# rgb-led-board.net
KiCad netlist of a schematic drawn in EAGLE
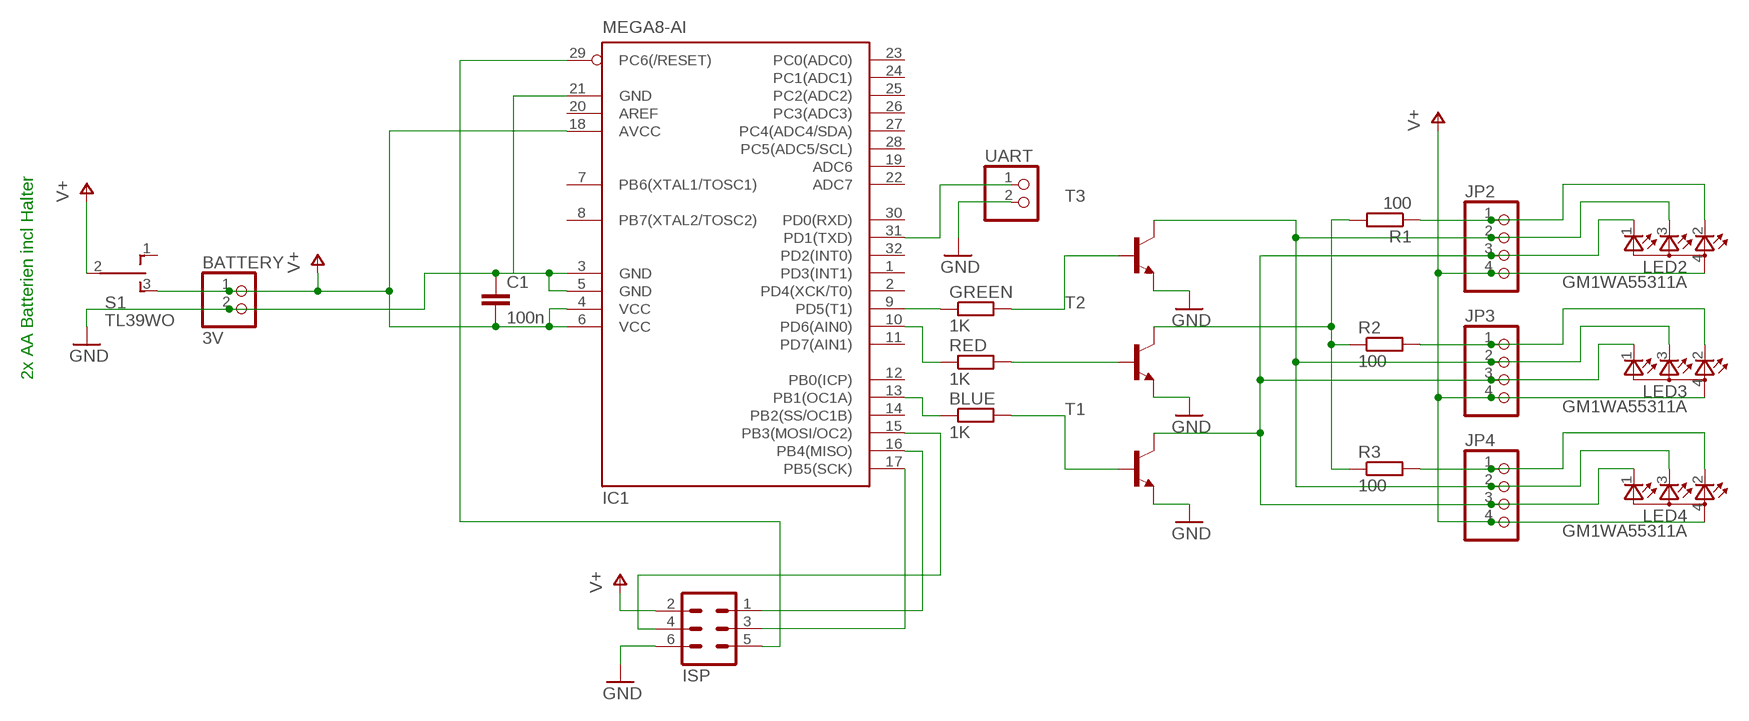
[diagram p0: schematic, sheet 1]

(export (version "E")
  (design (tool "Eeschema 10.0.6"))
  (components
    (comp (ref "BATTERY")
      (value "3V")
      (footprint "eagle-import:1X02")
      (libsource (lib "eagle-import") (part "PINHD-1X2"))
    )
    (comp (ref "BLUE")
      (value "1K")
      (footprint "eagle-import:R1206")
      (libsource (lib "eagle-import") (part "R-EU_R1206"))
    )
    (comp (ref "C1")
      (value "100n")
      (footprint "eagle-import:C1206")
      (libsource (lib "eagle-import") (part "C-EUC1206"))
    )
    (comp (ref "GREEN")
      (value "1K")
      (footprint "eagle-import:R1206")
      (libsource (lib "eagle-import") (part "R-EU_R1206"))
    )
    (comp (ref "IC1")
      (value "MEGA8-AI")
      (footprint "eagle-import:TQFP32-08")
      (fields (field (name "MPN") "ATMEGA8-16AU"))
      (libsource (lib "eagle-import") (part "MEGA8-AI"))
    )
    (comp (ref "ISP")
      (value "ML6")
      (footprint "eagle-import:ML6")
      (libsource (lib "eagle-import") (part "ML6"))
    )
    (comp (ref "JP2")
      (value "PINHD-1X4")
      (footprint "eagle-import:1X04")
      (libsource (lib "eagle-import") (part "PINHD-1X4"))
    )
    (comp (ref "JP3")
      (value "PINHD-1X4")
      (footprint "eagle-import:1X04")
      (libsource (lib "eagle-import") (part "PINHD-1X4"))
    )
    (comp (ref "JP4")
      (value "PINHD-1X4")
      (footprint "eagle-import:1X04")
      (libsource (lib "eagle-import") (part "PINHD-1X4"))
    )
    (comp (ref "LED2")
      (value "GM1WA55311A")
      (footprint "eagle-import:GM1WA55311A")
      (libsource (lib "eagle-import") (part "GM1WA55311A"))
    )
    (comp (ref "LED3")
      (value "GM1WA55311A")
      (footprint "eagle-import:GM1WA55311A")
      (libsource (lib "eagle-import") (part "GM1WA55311A"))
    )
    (comp (ref "LED4")
      (value "GM1WA55311A")
      (footprint "eagle-import:GM1WA55311A")
      (libsource (lib "eagle-import") (part "GM1WA55311A"))
    )
    (comp (ref "R1")
      (value "100")
      (footprint "eagle-import:R1206")
      (libsource (lib "eagle-import") (part "R-EU_R1206"))
    )
    (comp (ref "R2")
      (value "100")
      (footprint "eagle-import:R1206")
      (libsource (lib "eagle-import") (part "R-EU_R1206"))
    )
    (comp (ref "R3")
      (value "100")
      (footprint "eagle-import:R1206")
      (libsource (lib "eagle-import") (part "R-EU_R1206"))
    )
    (comp (ref "RED")
      (value "1K")
      (footprint "eagle-import:R1206")
      (libsource (lib "eagle-import") (part "R-EU_R1206"))
    )
    (comp (ref "S1")
      (value "TL39WO")
      (footprint "eagle-import:TL3XWO")
      (libsource (lib "eagle-import") (part "TL39WO"))
    )
    (comp (ref "T1")
      (value "BC817-16-NPN-SOT23-BEC")
      (footprint "eagle-import:SOT23-BEC")
      (libsource (lib "eagle-import") (part "-NPN-SOT23-BECBC817-16"))
    )
    (comp (ref "T2")
      (value "BC817-16-NPN-SOT23-BEC")
      (footprint "eagle-import:SOT23-BEC")
      (libsource (lib "eagle-import") (part "-NPN-SOT23-BECBC817-16"))
    )
    (comp (ref "T3")
      (value "BC817-16-NPN-SOT23-BEC")
      (footprint "eagle-import:SOT23-BEC")
      (libsource (lib "eagle-import") (part "-NPN-SOT23-BECBC817-16"))
    )
    (comp (ref "UART")
      (value "PINHD-1X2")
      (footprint "eagle-import:1X02")
      (libsource (lib "eagle-import") (part "PINHD-1X2"))
    )
  )
  (nets
    (net (code "1") (name "GND") (class "Default")
      (node (ref "BATTERY") (pin "2") (pinfunction "2_2") (pintype "passive"))
      (node (ref "C1") (pin "1") (pinfunction "1_1") (pintype "passive"))
      (node (ref "IC1") (pin "21") (pinfunction "GND_21") (pintype "power_in"))
      (node (ref "IC1") (pin "3") (pinfunction "GND_3") (pintype "power_in"))
      (node (ref "IC1") (pin "5") (pinfunction "GND_5") (pintype "power_in"))
      (node (ref "ISP") (pin "6") (pinfunction "6_6") (pintype "passive"))
      (node (ref "T1") (pin "E") (pinfunction "E_E") (pintype "passive"))
      (node (ref "T2") (pin "E") (pinfunction "E_E") (pintype "passive"))
      (node (ref "T3") (pin "E") (pinfunction "E_E") (pintype "passive"))
      (node (ref "UART") (pin "2") (pinfunction "2_2") (pintype "passive"))
    )
    (net (code "2") (name "Net-(BLUE-Pad2)") (class "Default")
      (node (ref "BLUE") (pin "2") (pinfunction "2_2") (pintype "passive"))
      (node (ref "T1") (pin "B") (pinfunction "B_B") (pintype "passive"))
    )
    (net (code "3") (name "Net-(GREEN-Pad2)") (class "Default")
      (node (ref "GREEN") (pin "2") (pinfunction "2_2") (pintype "passive"))
      (node (ref "T3") (pin "B") (pinfunction "B_B") (pintype "passive"))
    )
    (net (code "4") (name "Net-(IC1-PB1(OC1A))") (class "Default")
      (node (ref "BLUE") (pin "1") (pinfunction "1_1") (pintype "passive"))
      (node (ref "IC1") (pin "13") (pinfunction "PB1(OC1A)_13") (pintype "bidirectional"))
    )
    (net (code "5") (name "Net-(IC1-PB3(MOSI{slash}OC2))") (class "Default")
      (node (ref "IC1") (pin "15") (pinfunction "PB3(MOSI/OC2)_15") (pintype "bidirectional"))
      (node (ref "ISP") (pin "4") (pinfunction "4_4") (pintype "passive"))
    )
    (net (code "6") (name "Net-(IC1-PB4(MISO))") (class "Default")
      (node (ref "IC1") (pin "16") (pinfunction "PB4(MISO)_16") (pintype "bidirectional"))
      (node (ref "ISP") (pin "1") (pinfunction "1_1") (pintype "passive"))
    )
    (net (code "7") (name "Net-(IC1-PB5(SCK))") (class "Default")
      (node (ref "IC1") (pin "17") (pinfunction "PB5(SCK)_17") (pintype "bidirectional"))
      (node (ref "ISP") (pin "3") (pinfunction "3_3") (pintype "passive"))
    )
    (net (code "8") (name "Net-(IC1-PC6({slash}RESET))") (class "Default")
      (node (ref "IC1") (pin "29") (pinfunction "PC6(/RESET)_29") (pintype "bidirectional"))
      (node (ref "ISP") (pin "5") (pinfunction "5_5") (pintype "passive"))
    )
    (net (code "9") (name "Net-(IC1-PD1(TXD))") (class "Default")
      (node (ref "IC1") (pin "31") (pinfunction "PD1(TXD)_31") (pintype "bidirectional"))
      (node (ref "UART") (pin "1") (pinfunction "1_1") (pintype "passive"))
    )
    (net (code "10") (name "Net-(IC1-PD5(T1))") (class "Default")
      (node (ref "GREEN") (pin "1") (pinfunction "1_1") (pintype "passive"))
      (node (ref "IC1") (pin "9") (pinfunction "PD5(T1)_9") (pintype "bidirectional"))
    )
    (net (code "11") (name "Net-(IC1-PD6(AIN0))") (class "Default")
      (node (ref "IC1") (pin "10") (pinfunction "PD6(AIN0)_10") (pintype "bidirectional"))
      (node (ref "RED") (pin "1") (pinfunction "1_1") (pintype "passive"))
    )
    (net (code "12") (name "Net-(LED2-CBLUE)") (class "Default")
      (node (ref "JP2") (pin "2") (pinfunction "2_2") (pintype "passive"))
      (node (ref "JP3") (pin "2") (pinfunction "2_2") (pintype "passive"))
      (node (ref "JP4") (pin "2") (pinfunction "2_2") (pintype "passive"))
      (node (ref "LED2") (pin "3") (pinfunction "CBLUE_3") (pintype "passive"))
      (node (ref "LED3") (pin "3") (pinfunction "CBLUE_3") (pintype "passive"))
      (node (ref "LED4") (pin "3") (pinfunction "CBLUE_3") (pintype "passive"))
      (node (ref "T3") (pin "C") (pinfunction "C_C") (pintype "passive"))
    )
    (net (code "13") (name "Net-(LED2-CGREEN)") (class "Default")
      (node (ref "JP2") (pin "3") (pinfunction "3_3") (pintype "passive"))
      (node (ref "JP3") (pin "3") (pinfunction "3_3") (pintype "passive"))
      (node (ref "JP4") (pin "3") (pinfunction "3_3") (pintype "passive"))
      (node (ref "LED2") (pin "1") (pinfunction "CGREEN_1") (pintype "passive"))
      (node (ref "LED3") (pin "1") (pinfunction "CGREEN_1") (pintype "passive"))
      (node (ref "LED4") (pin "1") (pinfunction "CGREEN_1") (pintype "passive"))
      (node (ref "T1") (pin "C") (pinfunction "C_C") (pintype "passive"))
    )
    (net (code "14") (name "Net-(LED2-CRED)") (class "Default")
      (node (ref "JP2") (pin "1") (pinfunction "1_1") (pintype "passive"))
      (node (ref "LED2") (pin "2") (pinfunction "CRED_2") (pintype "passive"))
      (node (ref "R1") (pin "1") (pinfunction "1_1") (pintype "passive"))
    )
    (net (code "15") (name "Net-(LED3-CRED)") (class "Default")
      (node (ref "JP3") (pin "1") (pinfunction "1_1") (pintype "passive"))
      (node (ref "LED3") (pin "2") (pinfunction "CRED_2") (pintype "passive"))
      (node (ref "R2") (pin "2") (pinfunction "2_2") (pintype "passive"))
    )
    (net (code "16") (name "Net-(LED4-CRED)") (class "Default")
      (node (ref "JP4") (pin "1") (pinfunction "1_1") (pintype "passive"))
      (node (ref "LED4") (pin "2") (pinfunction "CRED_2") (pintype "passive"))
      (node (ref "R3") (pin "2") (pinfunction "2_2") (pintype "passive"))
    )
    (net (code "17") (name "Net-(R1-Pad2)") (class "Default")
      (node (ref "R1") (pin "2") (pinfunction "2_2") (pintype "passive"))
      (node (ref "R2") (pin "1") (pinfunction "1_1") (pintype "passive"))
      (node (ref "R3") (pin "1") (pinfunction "1_1") (pintype "passive"))
      (node (ref "T2") (pin "C") (pinfunction "C_C") (pintype "passive"))
    )
    (net (code "18") (name "Net-(RED-Pad2)") (class "Default")
      (node (ref "RED") (pin "2") (pinfunction "2_2") (pintype "passive"))
      (node (ref "T2") (pin "B") (pinfunction "B_B") (pintype "passive"))
    )
    (net (code "19") (name "V+") (class "Default")
      (node (ref "BATTERY") (pin "1") (pinfunction "1_1") (pintype "passive"))
      (node (ref "C1") (pin "2") (pinfunction "2_2") (pintype "passive"))
      (node (ref "IC1") (pin "18") (pinfunction "AVCC_18") (pintype "power_in"))
      (node (ref "IC1") (pin "4") (pinfunction "VCC_4") (pintype "power_in"))
      (node (ref "IC1") (pin "6") (pinfunction "VCC_6") (pintype "power_in"))
      (node (ref "ISP") (pin "2") (pinfunction "2_2") (pintype "passive"))
      (node (ref "JP2") (pin "4") (pinfunction "4_4") (pintype "passive"))
      (node (ref "JP3") (pin "4") (pinfunction "4_4") (pintype "passive"))
      (node (ref "JP4") (pin "4") (pinfunction "4_4") (pintype "passive"))
      (node (ref "LED2") (pin "4") (pinfunction "A_4") (pintype "passive"))
      (node (ref "LED3") (pin "4") (pinfunction "A_4") (pintype "passive"))
      (node (ref "LED4") (pin "4") (pinfunction "A_4") (pintype "passive"))
      (node (ref "S1") (pin "2") (pinfunction "P_2") (pintype "passive"))
      (node (ref "S1") (pin "3") (pinfunction "S_3") (pintype "passive"))
    )
    (net (code "20") (name "unconnected-(IC1-ADC6-Pad19)") (class "Default")
      (node (ref "IC1") (pin "19") (pinfunction "ADC6_19") (pintype "bidirectional"))
    )
    (net (code "21") (name "unconnected-(IC1-ADC7-Pad22)") (class "Default")
      (node (ref "IC1") (pin "22") (pinfunction "ADC7_22") (pintype "bidirectional"))
    )
    (net (code "22") (name "unconnected-(IC1-AREF-Pad20)") (class "Default")
      (node (ref "IC1") (pin "20") (pinfunction "AREF_20") (pintype "passive"))
    )
    (net (code "23") (name "unconnected-(IC1-PB0(ICP)-Pad12)") (class "Default")
      (node (ref "IC1") (pin "12") (pinfunction "PB0(ICP)_12") (pintype "bidirectional"))
    )
    (net (code "24") (name "unconnected-(IC1-PB2(SS{slash}OC1B)-Pad14)") (class "Default")
      (node (ref "IC1") (pin "14") (pinfunction "PB2(SS/OC1B)_14") (pintype "bidirectional"))
    )
    (net (code "25") (name "unconnected-(IC1-PB6(XTAL1{slash}TOSC1)-Pad7)") (class "Default")
      (node (ref "IC1") (pin "7") (pinfunction "PB6(XTAL1/TOSC1)_7") (pintype "bidirectional"))
    )
    (net (code "26") (name "unconnected-(IC1-PB7(XTAL2{slash}TOSC2)-Pad8)") (class "Default")
      (node (ref "IC1") (pin "8") (pinfunction "PB7(XTAL2/TOSC2)_8") (pintype "bidirectional"))
    )
    (net (code "27") (name "unconnected-(IC1-PC0(ADC0)-Pad23)") (class "Default")
      (node (ref "IC1") (pin "23") (pinfunction "PC0(ADC0)_23") (pintype "bidirectional"))
    )
    (net (code "28") (name "unconnected-(IC1-PC1(ADC1)-Pad24)") (class "Default")
      (node (ref "IC1") (pin "24") (pinfunction "PC1(ADC1)_24") (pintype "bidirectional"))
    )
    (net (code "29") (name "unconnected-(IC1-PC2(ADC2)-Pad25)") (class "Default")
      (node (ref "IC1") (pin "25") (pinfunction "PC2(ADC2)_25") (pintype "bidirectional"))
    )
    (net (code "30") (name "unconnected-(IC1-PC3(ADC3)-Pad26)") (class "Default")
      (node (ref "IC1") (pin "26") (pinfunction "PC3(ADC3)_26") (pintype "bidirectional"))
    )
    (net (code "31") (name "unconnected-(IC1-PC4(ADC4{slash}SDA)-Pad27)") (class "Default")
      (node (ref "IC1") (pin "27") (pinfunction "PC4(ADC4/SDA)_27") (pintype "bidirectional"))
    )
    (net (code "32") (name "unconnected-(IC1-PC5(ADC5{slash}SCL)-Pad28)") (class "Default")
      (node (ref "IC1") (pin "28") (pinfunction "PC5(ADC5/SCL)_28") (pintype "bidirectional"))
    )
    (net (code "33") (name "unconnected-(IC1-PD0(RXD)-Pad30)") (class "Default")
      (node (ref "IC1") (pin "30") (pinfunction "PD0(RXD)_30") (pintype "bidirectional"))
    )
    (net (code "34") (name "unconnected-(IC1-PD2(INT0)-Pad32)") (class "Default")
      (node (ref "IC1") (pin "32") (pinfunction "PD2(INT0)_32") (pintype "bidirectional"))
    )
    (net (code "35") (name "unconnected-(IC1-PD3(INT1)-Pad1)") (class "Default")
      (node (ref "IC1") (pin "1") (pinfunction "PD3(INT1)_1") (pintype "bidirectional"))
    )
    (net (code "36") (name "unconnected-(IC1-PD4(XCK{slash}T0)-Pad2)") (class "Default")
      (node (ref "IC1") (pin "2") (pinfunction "PD4(XCK/T0)_2") (pintype "bidirectional"))
    )
    (net (code "37") (name "unconnected-(IC1-PD7(AIN1)-Pad11)") (class "Default")
      (node (ref "IC1") (pin "11") (pinfunction "PD7(AIN1)_11") (pintype "bidirectional"))
    )
    (net (code "38") (name "unconnected-(S1-O-Pad1)") (class "Default")
      (node (ref "S1") (pin "1") (pinfunction "O_1") (pintype "passive"))
    )
  )
)
